# EPS_I2C-Repeater.net
KiCad netlist of a schematic drawn in Altium Designer
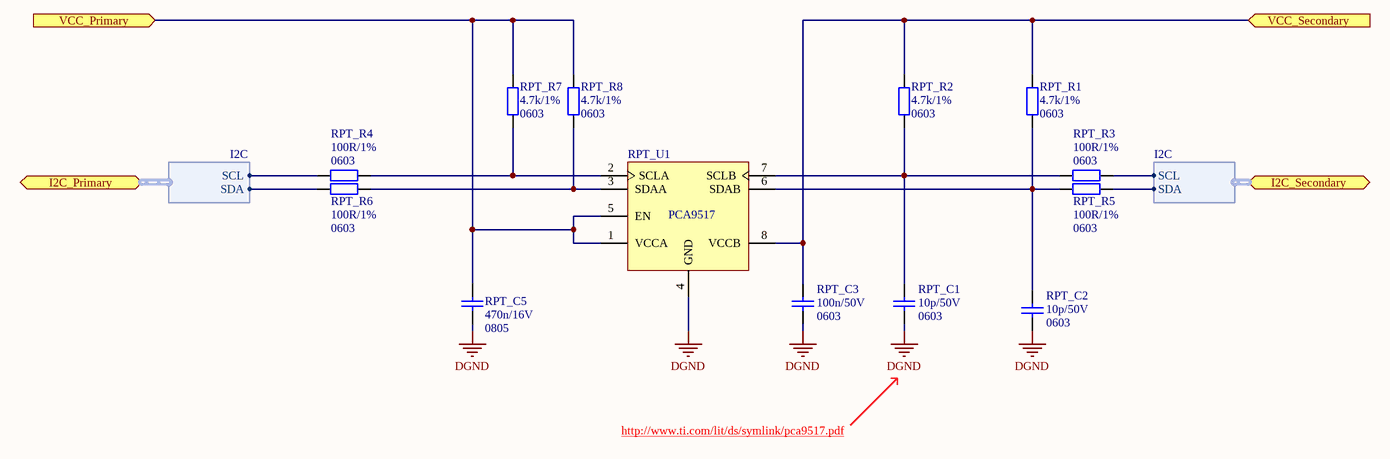
[diagram p0: EPS_I2C-Repeater.SchDoc]

(export (version "E")
  (design (tool "Eeschema 10.0.6"))
  (components
    (comp (ref "RPT_C1")
      (value "10p/50V")
      (footprint "SMD_Capacitor_0603")
      (description "Ceramic Cap Murata Automotive 10p/50V C0G 0603")
      (fields
        (field (name "MANUFACTURER") "Murata")
        (field (name "MANUFACTURERPARTNUMBER") "GCM1885C1H100JA16D")
        (field (name "PACKAGE") "0603")
      )
      (libsource (lib "capacitors") (part "Cer_GCM1885C1H100JA16D"))
    )
    (comp (ref "RPT_C2")
      (value "10p/50V")
      (footprint "SMD_Capacitor_0603")
      (description "Ceramic Cap Murata Automotive 10p/50V C0G 0603")
      (fields
        (field (name "MANUFACTURER") "Murata")
        (field (name "MANUFACTURERPARTNUMBER") "GCM1885C1H100JA16D")
        (field (name "PACKAGE") "0603")
      )
      (libsource (lib "capacitors") (part "Cer_GCM1885C1H100JA16D"))
    )
    (comp (ref "RPT_C3")
      (value "100n/50V")
      (footprint "SMD_Capacitor_0603")
      (description "Ceramic Cap Kemet COTS 100n/50V X7R 0603")
      (fields
        (field (name "MANUFACTURER") "Kemet")
        (field (name "MANUFACTURERPARTNUMBER") "C0603T104K5RALTU")
        (field (name "PACKAGE") "0603")
      )
      (libsource (lib "capacitors") (part "Cer_C0603T104K5RALTU"))
    )
    (comp (ref "RPT_C5")
      (value "470n/16V")
      (footprint "SMD_Capacitor_0805")
      (description "Cap")
      (fields (field (name "PACKAGE") "0805"))
      (libsource (lib "capacitors") (part "Cap"))
    )
    (comp (ref "RPT_R1")
      (value "4.7k/1%")
      (footprint "SMD_Resistor_0603")
      (description "4.7k/1% Vishay CRCW 0603 Resistor. 100mW, 100ppm, 75V.")
      (fields
        (field (name "MANUFACTURER") "Vishay")
        (field (name "MANUFACTUERPARTNUMBER") "CRCW06034K70FKxxxx")
        (field (name "PACKAGE") "0603")
      )
      (libsource (lib "resistors") (part "CRCW06034K70FKxxxx"))
    )
    (comp (ref "RPT_R2")
      (value "4.7k/1%")
      (footprint "SMD_Resistor_0603")
      (description "4.7k/1% Vishay CRCW 0603 Resistor. 100mW, 100ppm, 75V.")
      (fields
        (field (name "MANUFACTURER") "Vishay")
        (field (name "MANUFACTUERPARTNUMBER") "CRCW06034K70FKxxxx")
        (field (name "PACKAGE") "0603")
      )
      (libsource (lib "resistors") (part "CRCW06034K70FKxxxx"))
    )
    (comp (ref "RPT_R3")
      (value "100R/1%")
      (footprint "SMD_Resistor_0603")
      (description "100R/1% Vishay CRCW 0603 Resistor. 100mW, 100ppm, 75V.")
      (fields
        (field (name "MANUFACTURER") "Vishay")
        (field (name "MANUFACTURERPARTNUMBER") "CRCW0603100RFKxxxx")
        (field (name "PACKAGE") "0603")
      )
      (libsource (lib "resistors") (part "CRCW0603100RFKxxxx"))
    )
    (comp (ref "RPT_R4")
      (value "100R/1%")
      (footprint "SMD_Resistor_0603")
      (description "100R/1% Vishay CRCW 0603 Resistor. 100mW, 100ppm, 75V.")
      (fields
        (field (name "MANUFACTURER") "Vishay")
        (field (name "MANUFACTURERPARTNUMBER") "CRCW0603100RFKxxxx")
        (field (name "PACKAGE") "0603")
      )
      (libsource (lib "") (part "CRCW0603100RFKxxxx_1"))
    )
    (comp (ref "RPT_R5")
      (value "100R/1%")
      (footprint "SMD_Resistor_0603")
      (description "100R/1% Vishay CRCW 0603 Resistor. 100mW, 100ppm, 75V.")
      (fields
        (field (name "MANUFACTURER") "Vishay")
        (field (name "MANUFACTURERPARTNUMBER") "CRCW0603100RFKxxxx")
        (field (name "PACKAGE") "0603")
      )
      (libsource (lib "resistors") (part "CRCW0603100RFKxxxx"))
    )
    (comp (ref "RPT_R6")
      (value "100R/1%")
      (footprint "SMD_Resistor_0603")
      (description "100R/1% Vishay CRCW 0603 Resistor. 100mW, 100ppm, 75V.")
      (fields
        (field (name "MANUFACTURER") "Vishay")
        (field (name "MANUFACTURERPARTNUMBER") "CRCW0603100RFKxxxx")
        (field (name "PACKAGE") "0603")
      )
      (libsource (lib "") (part "CRCW0603100RFKxxxx_1"))
    )
    (comp (ref "RPT_R7")
      (value "4.7k/1%")
      (footprint "SMD_Resistor_0603")
      (description "4.7k/1% Vishay CRCW 0603 Resistor. 100mW, 100ppm, 75V.")
      (fields
        (field (name "MANUFACTURER") "Vishay")
        (field (name "MANUFACTUERPARTNUMBER") "CRCW06034K70FKxxxx")
        (field (name "PACKAGE") "0603")
      )
      (libsource (lib "") (part "CRCW06034K70FKxxxx_1"))
    )
    (comp (ref "RPT_R8")
      (value "4.7k/1%")
      (footprint "SMD_Resistor_0603")
      (description "4.7k/1% Vishay CRCW 0603 Resistor. 100mW, 100ppm, 75V.")
      (fields
        (field (name "MANUFACTURER") "Vishay")
        (field (name "MANUFACTUERPARTNUMBER") "CRCW06034K70FKxxxx")
        (field (name "PACKAGE") "0603")
      )
      (libsource (lib "resistors") (part "CRCW06034K70FKxxxx"))
    )
    (comp (ref "RPT_U1")
      (value "PCA9517")
      (footprint "TSSOP8_L")
      (description "Level-Translating I2C Bus Repeater")
      (fields
        (field (name "MANUFACTURER") "Texas Instruments")
        (field (name "MANUFACTURERPARTNUMBER") "PCA9517")
      )
      (libsource (lib "microcircuits") (part "PCA9517"))
    )
  )
  (nets
    (net (code "2") (name "/VCC_Primary") (class "Default")
      (node (ref "RPT_C5") (pin "1") (pinfunction "1_1") (pintype "passive"))
      (node (ref "RPT_R7") (pin "2") (pinfunction "2_2") (pintype "passive"))
      (node (ref "RPT_R8") (pin "1") (pinfunction "1_1") (pintype "passive"))
      (node (ref "RPT_U1") (pin "1") (pinfunction "VCCA_1") (pintype "passive"))
      (node (ref "RPT_U1") (pin "5") (pinfunction "EN_5") (pintype "passive"))
    )
    (net (code "3") (name "/VCC_Secondary") (class "Default")
      (node (ref "RPT_C3") (pin "2") (pinfunction "2_2") (pintype "passive"))
      (node (ref "RPT_R1") (pin "1") (pinfunction "1_1") (pintype "passive"))
      (node (ref "RPT_R2") (pin "1") (pinfunction "1_1") (pintype "passive"))
      (node (ref "RPT_U1") (pin "8") (pinfunction "VCCB_8") (pintype "passive"))
    )
    (net (code "5") (name "DGND") (class "Default")
      (node (ref "RPT_C1") (pin "2") (pinfunction "2_2") (pintype "passive"))
      (node (ref "RPT_C2") (pin "2") (pinfunction "2_2") (pintype "passive"))
      (node (ref "RPT_C3") (pin "1") (pinfunction "1_1") (pintype "passive"))
      (node (ref "RPT_C5") (pin "2") (pinfunction "2_2") (pintype "passive"))
      (node (ref "RPT_U1") (pin "4") (pinfunction "GND_4") (pintype "passive"))
    )
    (net (code "6") (name "Net-(RPT_U1-SCLA)") (class "Default")
      (node (ref "RPT_R4") (pin "1") (pinfunction "1_1") (pintype "passive"))
      (node (ref "RPT_R7") (pin "1") (pinfunction "1_1") (pintype "passive"))
      (node (ref "RPT_U1") (pin "2") (pinfunction "SCLA_2") (pintype "passive"))
    )
    (net (code "7") (name "Net-(RPT_U1-SCLB)") (class "Default")
      (node (ref "RPT_C1") (pin "1") (pinfunction "1_1") (pintype "passive"))
      (node (ref "RPT_R2") (pin "2") (pinfunction "2_2") (pintype "passive"))
      (node (ref "RPT_R3") (pin "1") (pinfunction "1_1") (pintype "passive"))
      (node (ref "RPT_U1") (pin "7") (pinfunction "SCLB_7") (pintype "passive"))
    )
    (net (code "8") (name "Net-(RPT_U1-SDAA)") (class "Default")
      (node (ref "RPT_R6") (pin "1") (pinfunction "1_1") (pintype "passive"))
      (node (ref "RPT_R8") (pin "2") (pinfunction "2_2") (pintype "passive"))
      (node (ref "RPT_U1") (pin "3") (pinfunction "SDAA_3") (pintype "passive"))
    )
    (net (code "9") (name "Net-(RPT_U1-SDAB)") (class "Default")
      (node (ref "RPT_C2") (pin "1") (pinfunction "1_1") (pintype "passive"))
      (node (ref "RPT_R1") (pin "2") (pinfunction "2_2") (pintype "passive"))
      (node (ref "RPT_R5") (pin "1") (pinfunction "1_1") (pintype "passive"))
      (node (ref "RPT_U1") (pin "6") (pinfunction "SDAB_6") (pintype "passive"))
    )
    (net (code "10") (name "unconnected-(RPT_R3-Pad2)") (class "Default")
      (node (ref "RPT_R3") (pin "2") (pinfunction "2_2") (pintype "passive"))
    )
    (net (code "11") (name "unconnected-(RPT_R4-Pad2)") (class "Default")
      (node (ref "RPT_R4") (pin "2") (pinfunction "2_2") (pintype "passive"))
    )
    (net (code "12") (name "unconnected-(RPT_R5-Pad2)") (class "Default")
      (node (ref "RPT_R5") (pin "2") (pinfunction "2_2") (pintype "passive"))
    )
    (net (code "13") (name "unconnected-(RPT_R6-Pad2)") (class "Default")
      (node (ref "RPT_R6") (pin "2") (pinfunction "2_2") (pintype "passive"))
    )
  )
)
